# revision_1_2.net
KiCad netlist of a schematic drawn in EAGLE
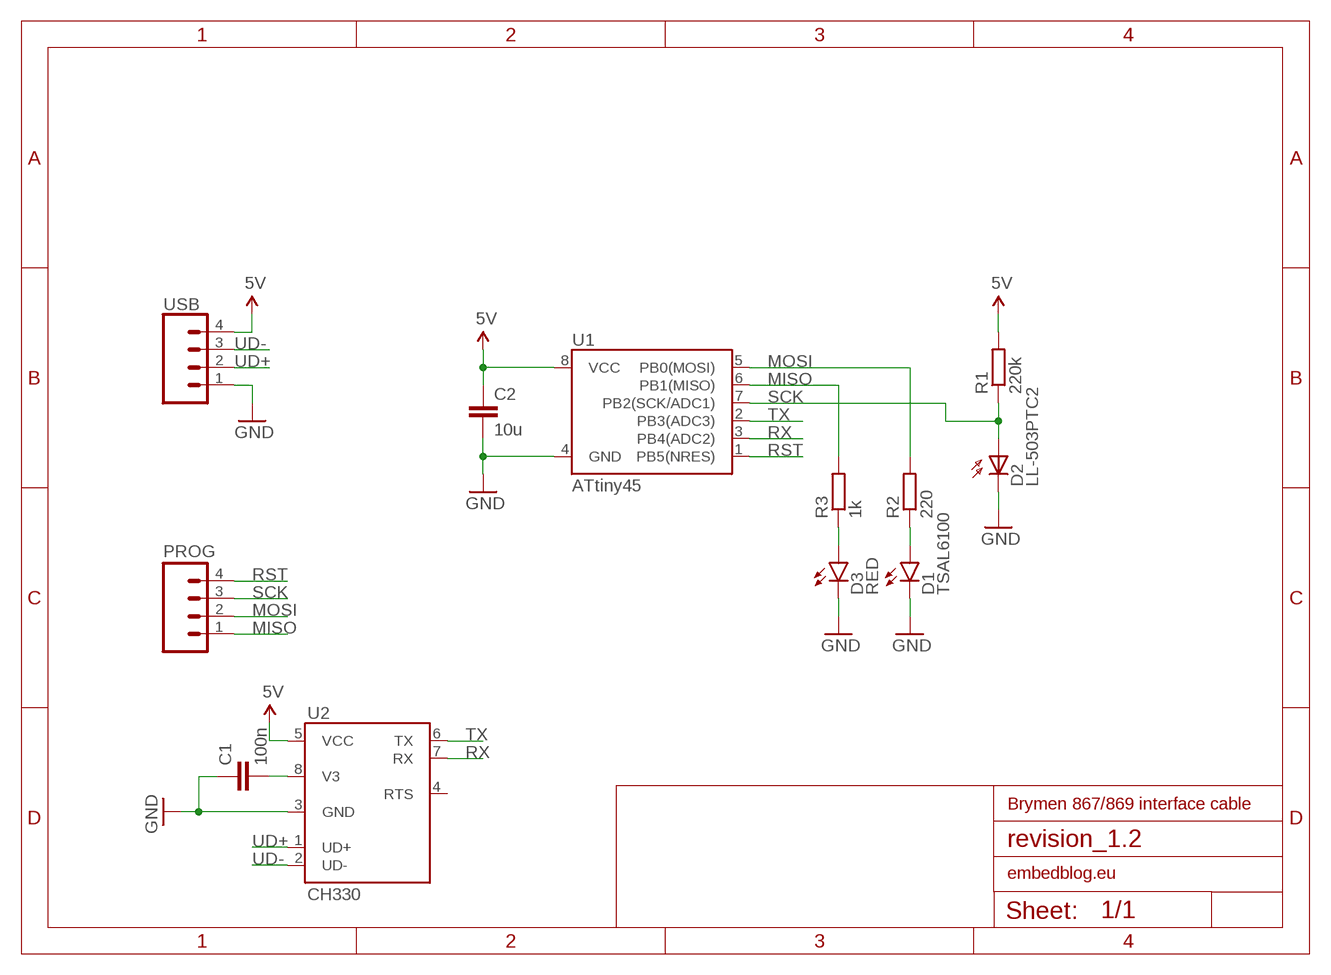
[diagram p0: schematic, sheet 1]

(export (version "E")
  (design (tool "Eeschema 10.0.6"))
  (components
    (comp (ref "C1")
      (value "100n")
      (footprint "eagle-import:C0805")
      (libsource (lib "eagle-import") (part "C-EUC0805"))
    )
    (comp (ref "C2")
      (value "10u")
      (footprint "eagle-import:C0805")
      (libsource (lib "eagle-import") (part "C-EUC0805"))
    )
    (comp (ref "D1")
      (value "TSAL6100")
      (footprint "eagle-import:LED5MM")
      (libsource (lib "eagle-import") (part "LED5MM"))
    )
    (comp (ref "D2")
      (value "LL-503PTC2")
      (footprint "eagle-import:BPX65")
      (fields (field (name "MPN") "BPX65."))
      (libsource (lib "eagle-import") (part "BPX65"))
    )
    (comp (ref "D3")
      (value "RED")
      (footprint "eagle-import:LED-1206")
      (libsource (lib "eagle-import") (part "LED1206"))
    )
    (comp (ref "PROG")
      (value "M04NO_SILK_ALL_ROUND")
      (footprint "eagle-import:1X04_NO_SILK_ALL_ROUND")
      (libsource (lib "eagle-import") (part "M04NO_SILK_ALL_ROUND"))
    )
    (comp (ref "R1")
      (value "220k")
      (footprint "eagle-import:R0805")
      (libsource (lib "eagle-import") (part "R-EU_R0805"))
    )
    (comp (ref "R2")
      (value "220")
      (footprint "eagle-import:R0805")
      (libsource (lib "eagle-import") (part "R-EU_R0805"))
    )
    (comp (ref "R3")
      (value "1k")
      (footprint "eagle-import:R0805")
      (libsource (lib "eagle-import") (part "R-EU_R0805"))
    )
    (comp (ref "U1")
      (value "ATtiny45")
      (footprint "eagle-import:SO08-EIAJ")
      (libsource (lib "eagle-import") (part "ATTINY45TINY85-20-SMT"))
    )
    (comp (ref "U2")
      (value "CH330")
      (footprint "eagle-import:SO08")
      (libsource (lib "eagle-import") (part "CH330"))
    )
    (comp (ref "USB")
      (value "CONN_04")
      (footprint "eagle-import:1X04")
      (libsource (lib "eagle-import") (part "CONN_04"))
    )
  )
  (nets
    (net (code "1") (name "/MISO") (class "Default")
      (node (ref "PROG") (pin "1") (pinfunction "1_1") (pintype "passive"))
      (node (ref "R3") (pin "2") (pinfunction "2_2") (pintype "passive"))
      (node (ref "U1") (pin "6") (pinfunction "PB1(MISO)_6") (pintype "bidirectional"))
    )
    (net (code "2") (name "/MOSI") (class "Default")
      (node (ref "PROG") (pin "2") (pinfunction "2_2") (pintype "passive"))
      (node (ref "R2") (pin "2") (pinfunction "2_2") (pintype "passive"))
      (node (ref "U1") (pin "5") (pinfunction "PB0(MOSI)_5") (pintype "bidirectional"))
    )
    (net (code "3") (name "/RST") (class "Default")
      (node (ref "PROG") (pin "4") (pinfunction "4_4") (pintype "passive"))
      (node (ref "U1") (pin "1") (pinfunction "PB5(NRES)_1") (pintype "bidirectional"))
    )
    (net (code "4") (name "/RX") (class "Default")
      (node (ref "U1") (pin "3") (pinfunction "PB4(ADC2)_3") (pintype "bidirectional"))
      (node (ref "U2") (pin "7") (pinfunction "RX_7") (pintype "bidirectional"))
    )
    (net (code "5") (name "/SCK") (class "Default")
      (node (ref "D2") (pin "A") (pinfunction "A_A") (pintype "passive"))
      (node (ref "PROG") (pin "3") (pinfunction "3_3") (pintype "passive"))
      (node (ref "R1") (pin "1") (pinfunction "1_1") (pintype "passive"))
      (node (ref "U1") (pin "7") (pinfunction "PB2(SCK/ADC1)_7") (pintype "bidirectional"))
    )
    (net (code "6") (name "/TX") (class "Default")
      (node (ref "U1") (pin "2") (pinfunction "PB3(ADC3)_2") (pintype "bidirectional"))
      (node (ref "U2") (pin "6") (pinfunction "TX_6") (pintype "bidirectional"))
    )
    (net (code "7") (name "/UD+") (class "Default")
      (node (ref "U2") (pin "1") (pinfunction "UD+_1") (pintype "bidirectional"))
      (node (ref "USB") (pin "2") (pinfunction "2_2") (pintype "passive"))
    )
    (net (code "8") (name "/UD-") (class "Default")
      (node (ref "U2") (pin "2") (pinfunction "UD-_2") (pintype "bidirectional"))
      (node (ref "USB") (pin "3") (pinfunction "3_3") (pintype "passive"))
    )
    (net (code "9") (name "5V") (class "Default")
      (node (ref "C2") (pin "1") (pinfunction "1_1") (pintype "passive"))
      (node (ref "R1") (pin "2") (pinfunction "2_2") (pintype "passive"))
      (node (ref "U1") (pin "8") (pinfunction "VCC_8") (pintype "bidirectional"))
      (node (ref "U2") (pin "5") (pinfunction "VCC_5") (pintype "bidirectional"))
      (node (ref "USB") (pin "4") (pinfunction "4_4") (pintype "passive"))
    )
    (net (code "10") (name "GND") (class "Default")
      (node (ref "C1") (pin "1") (pinfunction "1_1") (pintype "passive"))
      (node (ref "C2") (pin "2") (pinfunction "2_2") (pintype "passive"))
      (node (ref "D1") (pin "K") (pinfunction "C_K") (pintype "passive"))
      (node (ref "D2") (pin "K") (pinfunction "C_K") (pintype "passive"))
      (node (ref "D3") (pin "C") (pinfunction "C_C") (pintype "passive"))
      (node (ref "U1") (pin "4") (pinfunction "GND_4") (pintype "bidirectional"))
      (node (ref "U2") (pin "3") (pinfunction "GND_3") (pintype "bidirectional"))
      (node (ref "USB") (pin "1") (pinfunction "1_1") (pintype "passive"))
    )
    (net (code "11") (name "Net-(D1-PadA)") (class "Default")
      (node (ref "D1") (pin "A") (pinfunction "A_A") (pintype "passive"))
      (node (ref "R2") (pin "1") (pinfunction "1_1") (pintype "passive"))
    )
    (net (code "12") (name "Net-(D3-PadA)") (class "Default")
      (node (ref "D3") (pin "A") (pinfunction "A_A") (pintype "passive"))
      (node (ref "R3") (pin "1") (pinfunction "1_1") (pintype "passive"))
    )
    (net (code "13") (name "Net-(U2-V3)") (class "Default")
      (node (ref "C1") (pin "2") (pinfunction "2_2") (pintype "passive"))
      (node (ref "U2") (pin "8") (pinfunction "V3_8") (pintype "bidirectional"))
    )
    (net (code "14") (name "unconnected-(U2-RTS-Pad4)") (class "Default")
      (node (ref "U2") (pin "4") (pinfunction "RTS_4") (pintype "bidirectional"))
    )
  )
)
